# MRAM.net
KiCad netlist of a schematic drawn in Altium Designer
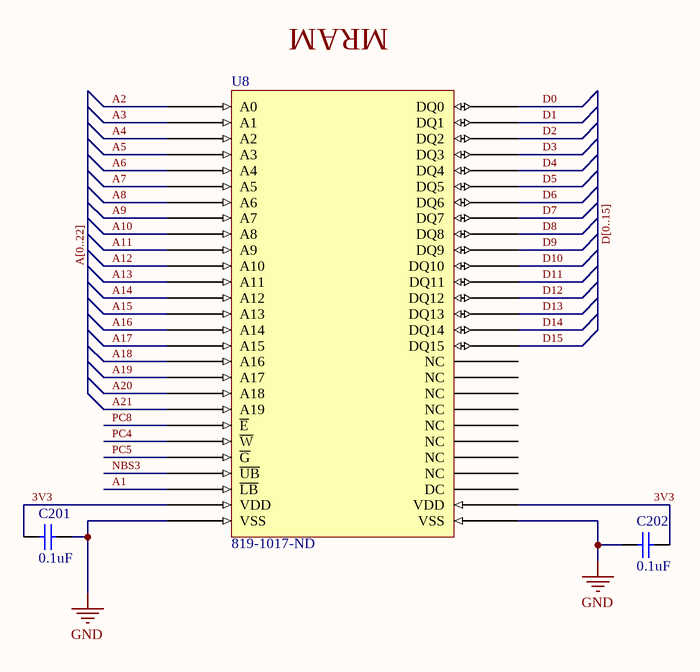
[diagram p0: MRAM.SchDoc]

(export (version "E")
  (design (tool "Eeschema 10.0.6"))
  (components
    (comp (ref "C201")
      (value "0.1uF")
      (footprint "CAPC2008X06N")
      (description "CAP CER 0.1UF 50V 10% X7R 0805")
      (fields (field (name "Comment") "Kemet_0805_a_0.1uF"))
      (libsource (lib "Capacitors") (part "Kemet_0805_a_0.1uF"))
    )
    (comp (ref "C202")
      (value "0.1uF")
      (footprint "CAPC2008X06N")
      (description "CAP CER 0.1UF 50V 10% X7R 0805")
      (fields (field (name "Comment") "Kemet_0805_a_0.1uF"))
      (libsource (lib "Capacitors") (part "Kemet_0805_a_0.1uF"))
    )
    (comp (ref "U8")
      (value "MRAM (Magnetoresistive RAM)")
      (footprint "TSOP80P1180X120_HS-54N")
      (description "IC MRAM 16MBIT 35NS 54TSOP")
      (fields (field (name "SUPPLIER PART NUMBER 1") "819-1017-ND"))
      (libsource (lib "Everspin Technologies") (part "MR4A16BCYS35"))
    )
  )
  (nets
    (net (code "3") (name "/3V3") (class "Default")
      (node (ref "C201") (pin "1") (pinfunction "1_1") (pintype "passive"))
      (node (ref "C202") (pin "2") (pinfunction "2_2") (pintype "passive"))
      (node (ref "U8") (pin "13") (pinfunction "VDD_13") (pintype "input"))
      (node (ref "U8") (pin "41") (pinfunction "VDD_41") (pintype "input"))
    )
    (net (code "4") (name "/A1") (class "Default")
      (node (ref "U8") (pin "47") (pinfunction "~{LB}_47") (pintype "input"))
    )
    (net (code "5") (name "/A2") (class "Default")
      (node (ref "U8") (pin "3") (pinfunction "A0_3") (pintype "input"))
    )
    (net (code "6") (name "/A3") (class "Default")
      (node (ref "U8") (pin "4") (pinfunction "A1_4") (pintype "input"))
    )
    (net (code "7") (name "/A4") (class "Default")
      (node (ref "U8") (pin "5") (pinfunction "A2_5") (pintype "input"))
    )
    (net (code "8") (name "/A5") (class "Default")
      (node (ref "U8") (pin "6") (pinfunction "A3_6") (pintype "input"))
    )
    (net (code "9") (name "/A6") (class "Default")
      (node (ref "U8") (pin "7") (pinfunction "A4_7") (pintype "input"))
    )
    (net (code "10") (name "/A7") (class "Default")
      (node (ref "U8") (pin "20") (pinfunction "A5_20") (pintype "input"))
    )
    (net (code "11") (name "/A8") (class "Default")
      (node (ref "U8") (pin "21") (pinfunction "A6_21") (pintype "input"))
    )
    (net (code "12") (name "/A9") (class "Default")
      (node (ref "U8") (pin "22") (pinfunction "A7_22") (pintype "input"))
    )
    (net (code "13") (name "/A10") (class "Default")
      (node (ref "U8") (pin "23") (pinfunction "A8_23") (pintype "input"))
    )
    (net (code "14") (name "/A11") (class "Default")
      (node (ref "U8") (pin "24") (pinfunction "A9_24") (pintype "input"))
    )
    (net (code "15") (name "/A12") (class "Default")
      (node (ref "U8") (pin "31") (pinfunction "A10_31") (pintype "input"))
    )
    (net (code "16") (name "/A13") (class "Default")
      (node (ref "U8") (pin "32") (pinfunction "A11_32") (pintype "input"))
    )
    (net (code "17") (name "/A14") (class "Default")
      (node (ref "U8") (pin "33") (pinfunction "A12_33") (pintype "input"))
    )
    (net (code "18") (name "/A15") (class "Default")
      (node (ref "U8") (pin "34") (pinfunction "A13_34") (pintype "input"))
    )
    (net (code "19") (name "/A16") (class "Default")
      (node (ref "U8") (pin "35") (pinfunction "A14_35") (pintype "input"))
    )
    (net (code "20") (name "/A17") (class "Default")
      (node (ref "U8") (pin "50") (pinfunction "A15_50") (pintype "input"))
    )
    (net (code "21") (name "/A18") (class "Default")
      (node (ref "U8") (pin "51") (pinfunction "A16_51") (pintype "input"))
    )
    (net (code "22") (name "/A19") (class "Default")
      (node (ref "U8") (pin "52") (pinfunction "A17_52") (pintype "input"))
    )
    (net (code "23") (name "/A20") (class "Default")
      (node (ref "U8") (pin "53") (pinfunction "A18_53") (pintype "input"))
    )
    (net (code "24") (name "/A21") (class "Default")
      (node (ref "U8") (pin "2") (pinfunction "A19_2") (pintype "input"))
    )
    (net (code "26") (name "/D0") (class "Default")
      (node (ref "U8") (pin "9") (pinfunction "DQ0_9") (pintype "bidirectional"))
    )
    (net (code "27") (name "/D1") (class "Default")
      (node (ref "U8") (pin "10") (pinfunction "DQ1_10") (pintype "bidirectional"))
    )
    (net (code "28") (name "/D2") (class "Default")
      (node (ref "U8") (pin "11") (pinfunction "DQ2_11") (pintype "bidirectional"))
    )
    (net (code "29") (name "/D3") (class "Default")
      (node (ref "U8") (pin "12") (pinfunction "DQ3_12") (pintype "bidirectional"))
    )
    (net (code "30") (name "/D4") (class "Default")
      (node (ref "U8") (pin "15") (pinfunction "DQ4_15") (pintype "bidirectional"))
    )
    (net (code "31") (name "/D5") (class "Default")
      (node (ref "U8") (pin "16") (pinfunction "DQ5_16") (pintype "bidirectional"))
    )
    (net (code "32") (name "/D6") (class "Default")
      (node (ref "U8") (pin "17") (pinfunction "DQ6_17") (pintype "bidirectional"))
    )
    (net (code "33") (name "/D7") (class "Default")
      (node (ref "U8") (pin "18") (pinfunction "DQ7_18") (pintype "bidirectional"))
    )
    (net (code "34") (name "/D8") (class "Default")
      (node (ref "U8") (pin "37") (pinfunction "DQ8_37") (pintype "bidirectional"))
    )
    (net (code "35") (name "/D9") (class "Default")
      (node (ref "U8") (pin "38") (pinfunction "DQ9_38") (pintype "bidirectional"))
    )
    (net (code "36") (name "/D10") (class "Default")
      (node (ref "U8") (pin "39") (pinfunction "DQ10_39") (pintype "bidirectional"))
    )
    (net (code "37") (name "/D11") (class "Default")
      (node (ref "U8") (pin "40") (pinfunction "DQ11_40") (pintype "bidirectional"))
    )
    (net (code "38") (name "/D12") (class "Default")
      (node (ref "U8") (pin "43") (pinfunction "DQ12_43") (pintype "bidirectional"))
    )
    (net (code "39") (name "/D13") (class "Default")
      (node (ref "U8") (pin "44") (pinfunction "DQ13_44") (pintype "bidirectional"))
    )
    (net (code "40") (name "/D14") (class "Default")
      (node (ref "U8") (pin "45") (pinfunction "DQ14_45") (pintype "bidirectional"))
    )
    (net (code "41") (name "/D15") (class "Default")
      (node (ref "U8") (pin "46") (pinfunction "DQ15_46") (pintype "bidirectional"))
    )
    (net (code "43") (name "/NBS3") (class "Default")
      (node (ref "U8") (pin "48") (pinfunction "~{UB}_48") (pintype "input"))
    )
    (net (code "44") (name "/PC4") (class "Default")
      (node (ref "U8") (pin "19") (pinfunction "~{W}_19") (pintype "input"))
    )
    (net (code "45") (name "/PC5") (class "Default")
      (node (ref "U8") (pin "49") (pinfunction "~{G}_49") (pintype "input"))
    )
    (net (code "46") (name "/PC8") (class "Default")
      (node (ref "U8") (pin "8") (pinfunction "~{E}_8") (pintype "input"))
    )
    (net (code "47") (name "GND") (class "Default")
      (node (ref "C201") (pin "2") (pinfunction "2_2") (pintype "passive"))
      (node (ref "C202") (pin "1") (pinfunction "1_1") (pintype "passive"))
      (node (ref "U8") (pin "14") (pinfunction "VSS_14") (pintype "input"))
      (node (ref "U8") (pin "42") (pinfunction "VSS_42") (pintype "input"))
    )
    (net (code "48") (name "unconnected-(U8-DC-Pad36)") (class "Default")
      (node (ref "U8") (pin "36") (pinfunction "DC_36") (pintype "passive"))
    )
    (net (code "49") (name "unconnected-(U8-NC-Pad1)") (class "Default")
      (node (ref "U8") (pin "1") (pinfunction "NC_1") (pintype "passive"))
    )
    (net (code "50") (name "unconnected-(U8-NC-Pad25)") (class "Default")
      (node (ref "U8") (pin "25") (pinfunction "NC_25") (pintype "passive"))
    )
    (net (code "51") (name "unconnected-(U8-NC-Pad26)") (class "Default")
      (node (ref "U8") (pin "26") (pinfunction "NC_26") (pintype "passive"))
    )
    (net (code "52") (name "unconnected-(U8-NC-Pad27)") (class "Default")
      (node (ref "U8") (pin "27") (pinfunction "NC_27") (pintype "passive"))
    )
    (net (code "53") (name "unconnected-(U8-NC-Pad28)") (class "Default")
      (node (ref "U8") (pin "28") (pinfunction "NC_28") (pintype "passive"))
    )
    (net (code "54") (name "unconnected-(U8-NC-Pad29)") (class "Default")
      (node (ref "U8") (pin "29") (pinfunction "NC_29") (pintype "passive"))
    )
    (net (code "55") (name "unconnected-(U8-NC-Pad30)") (class "Default")
      (node (ref "U8") (pin "30") (pinfunction "NC_30") (pintype "passive"))
    )
    (net (code "56") (name "unconnected-(U8-NC-Pad54)") (class "Default")
      (node (ref "U8") (pin "54") (pinfunction "NC_54") (pintype "passive"))
    )
  )
)
